# IsoPowerSupply.net
KiCad netlist of a schematic drawn in Altium Designer
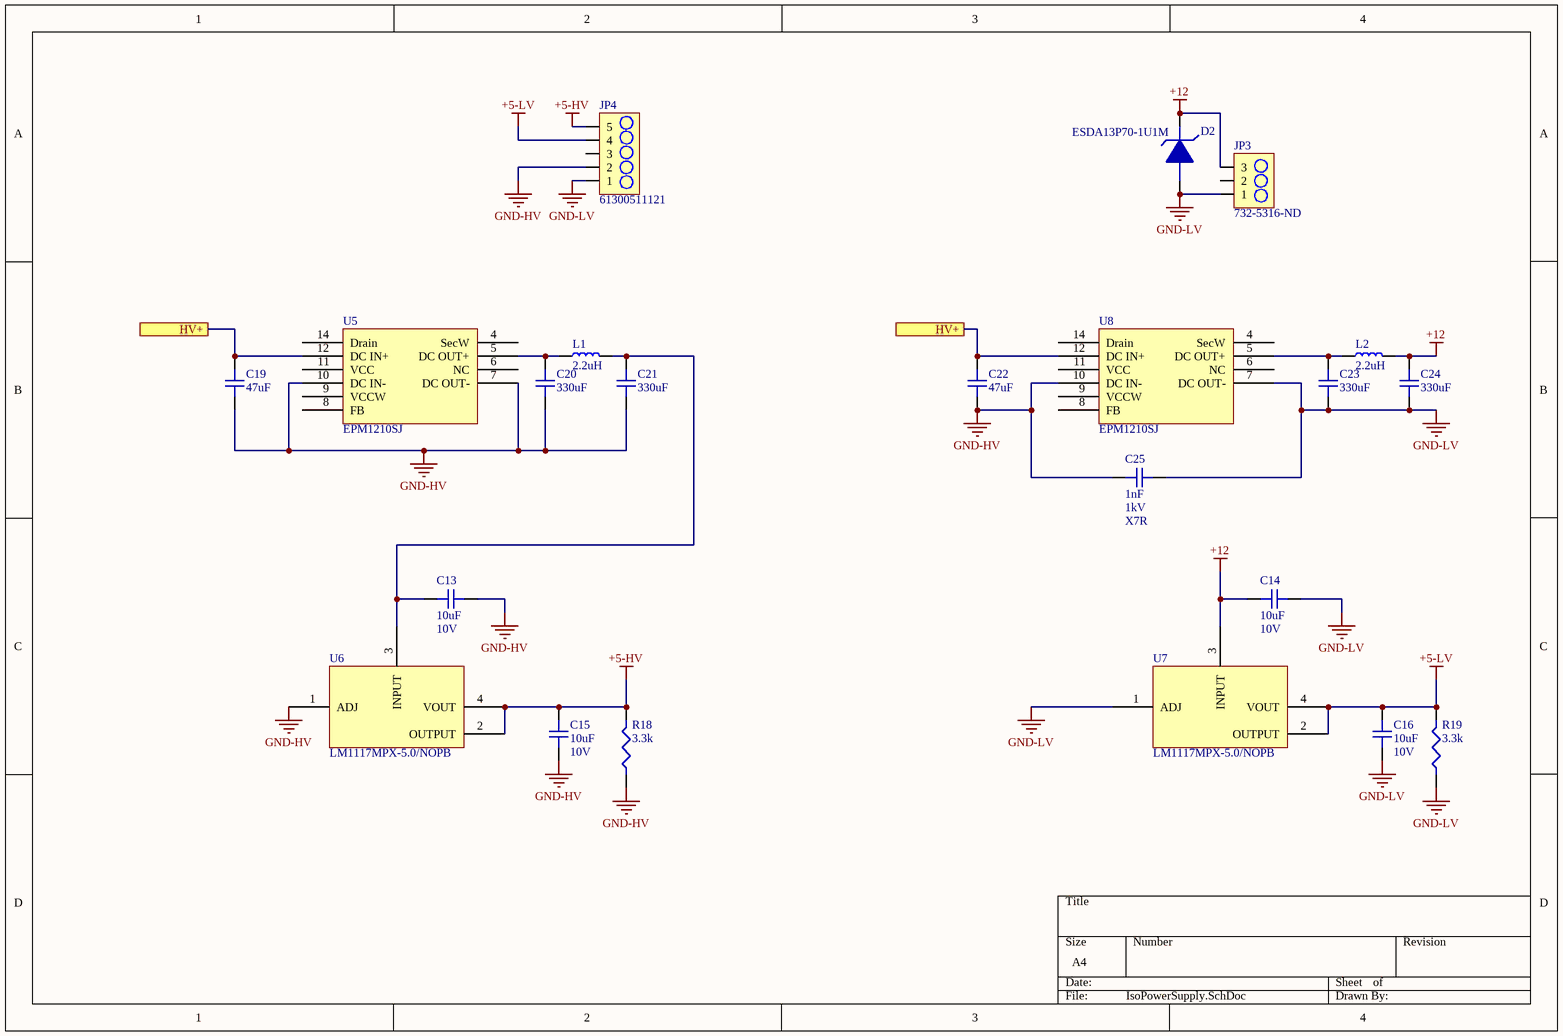
[diagram p0: IsoPowerSupply.SchDoc]

(export (version "E")
  (design (tool "Eeschema 10.0.6"))
  (components
    (comp (ref "C13")
      (value "10uF")
      (footprint "TANT_10u")
      (fields
        (field (name "MANUFACTURER") "Kyocera AVX")
        (field (name "MANUFACTURER PART NUMBER") "F381A106MMA")
        (field (name "TOLERANCE") "20%")
        (field (name "VOLTAGE RATING") "10V")
      )
      (libsource (lib "PHANTOM_LIBRARY") (part "F381A106MMA"))
    )
    (comp (ref "C14")
      (value "10uF")
      (footprint "TANT_10u")
      (fields
        (field (name "MANUFACTURER") "Kyocera AVX")
        (field (name "MANUFACTURER PART NUMBER") "F381A106MMA")
        (field (name "TOLERANCE") "20%")
        (field (name "VOLTAGE RATING") "10V")
      )
      (libsource (lib "PHANTOM_LIBRARY") (part "F381A106MMA"))
    )
    (comp (ref "C15")
      (value "10uF")
      (footprint "TANT_10u")
      (fields
        (field (name "MANUFACTURER") "Kyocera AVX")
        (field (name "MANUFACTURER PART NUMBER") "F381A106MMA")
        (field (name "TOLERANCE") "20%")
        (field (name "VOLTAGE RATING") "10V")
      )
      (libsource (lib "PHANTOM_LIBRARY") (part "F381A106MMA"))
    )
    (comp (ref "C16")
      (value "10uF")
      (footprint "TANT_10u")
      (fields
        (field (name "MANUFACTURER") "Kyocera AVX")
        (field (name "MANUFACTURER PART NUMBER") "F381A106MMA")
        (field (name "TOLERANCE") "20%")
        (field (name "VOLTAGE RATING") "10V")
      )
      (libsource (lib "PHANTOM_LIBRARY") (part "F381A106MMA"))
    )
    (comp (ref "C19")
      (value "47uF")
      (footprint "radial cap, 5mm spacing")
      (description "CAP  47µF 100V Aluminum Electrolytic Capacitors Radial, Can 2000 Hrs @ 85°C")
      (fields
        (field (name "MANUFACTURER") "Nichicon")
        (field (name "MANUFACTURER PART NUMBER") "UKL2A470KPD")
      )
      (libsource (lib "PHANTOM_LIBRARY") (part "UKL2A470KPD"))
    )
    (comp (ref "C20")
      (value "330uF")
      (footprint "radial cap, 5mm spacing")
      (description "CAP 330µF 50V Aluminum Electrolytic Capacitors Radial, Can 2000 Hrs @ 85°C")
      (fields
        (field (name "MANUFACTURER") "Nichicon")
        (field (name "MANUFACTURER PART NUMBER") "UKL1H331KHD")
      )
      (libsource (lib "PHANTOM_LIBRARY") (part "UKL1H331KHD"))
    )
    (comp (ref "C21")
      (value "330uF")
      (footprint "radial cap, 5mm spacing")
      (description "CAP 330µF 50V Aluminum Electrolytic Capacitors Radial, Can 2000 Hrs @ 85°C")
      (fields
        (field (name "MANUFACTURER") "Nichicon")
        (field (name "MANUFACTURER PART NUMBER") "UKL1H331KHD")
      )
      (libsource (lib "PHANTOM_LIBRARY") (part "UKL1H331KHD"))
    )
    (comp (ref "C22")
      (value "47uF")
      (footprint "radial cap, 5mm spacing")
      (description "CAP  47µF 100V Aluminum Electrolytic Capacitors Radial, Can 2000 Hrs @ 85°C")
      (fields
        (field (name "MANUFACTURER") "Nichicon")
        (field (name "MANUFACTURER PART NUMBER") "UKL2A470KPD")
      )
      (libsource (lib "PHANTOM_LIBRARY") (part "UKL2A470KPD"))
    )
    (comp (ref "C23")
      (value "330uF")
      (footprint "radial cap, 5mm spacing")
      (description "CAP 330µF 50V Aluminum Electrolytic Capacitors Radial, Can 2000 Hrs @ 85°C")
      (fields
        (field (name "MANUFACTURER") "Nichicon")
        (field (name "MANUFACTURER PART NUMBER") "UKL1H331KHD")
      )
      (libsource (lib "PHANTOM_LIBRARY") (part "UKL1H331KHD"))
    )
    (comp (ref "C24")
      (value "330uF")
      (footprint "radial cap, 5mm spacing")
      (description "CAP 330µF 50V Aluminum Electrolytic Capacitors Radial, Can 2000 Hrs @ 85°C")
      (fields
        (field (name "MANUFACTURER") "Nichicon")
        (field (name "MANUFACTURER PART NUMBER") "UKL1H331KHD")
      )
      (libsource (lib "PHANTOM_LIBRARY") (part "UKL1H331KHD"))
    )
    (comp (ref "C25")
      (value "1nF")
      (footprint "C1206")
      (description "CAP MLCC 1000PF 1KV X7R 1206 Series Comm. Isolation Caps")
      (fields
        (field (name "MANUFACTURER") "Yageo")
        (field (name "MANUFACTURER PART NUMBER") "CC1206KKX7RCBB102")
        (field (name "VOLTAGE RATING") "1kV")
        (field (name "DIELECTRIC") "X7R")
      )
      (libsource (lib "PHANTOM_LIBRARY") (part "CC1206KKX7RCBB102"))
    )
    (comp (ref "D2")
      (value "ESDA13P70-1U1M")
      (footprint "DIODE_TVS_0603")
      (description "TVS diode 12V, 20V Clamp 60A (8/20µs) Ipp Tvs Diode Surface Mount 1610")
      (fields (field (name "MANUFACTURER") "STMicroelectronics"))
      (libsource (lib "PHANTOM_LIBRARY") (part "ESDA13P70-1U1M"))
    )
    (comp (ref "JP3")
      (value "732-5316-ND")
      (footprint "3PIN_HEADER")
      (fields
        (field (name "MANUFACTURER") "Wurth Electronics")
        (field (name "MANUFACTURER PART NUMBER") "61300311121")
      )
      (libsource (lib "PHANTOM_LIBRARY") (part "61300311121"))
    )
    (comp (ref "JP4")
      (value "61300511121")
      (footprint "5PIN_HEADER")
      (fields (field (name "MANUFACTURER") "Wurth Electronics"))
      (libsource (lib "PHANTOM_LIBRARY") (part "61300511121"))
    )
    (comp (ref "L1")
      (value "2.2uH")
      (footprint "L0805")
      (description "IND 2.2µH Shielded Wirewound Inductor 1.2A 228mOhm Max 0805 (2012 Metric)")
      (fields
        (field (name "MANUFACTURER") "Murata")
        (field (name "MANUFACTURER PART NUMBER") "DFE201210U-2R2M=P2")
      )
      (libsource (lib "PHANTOM_LIBRARY") (part "DFE201210U-2R2M=P2"))
    )
    (comp (ref "L2")
      (value "2.2uH")
      (footprint "L0805")
      (description "IND 2.2µH Shielded Wirewound Inductor 1.2A 228mOhm Max 0805 (2012 Metric)")
      (fields
        (field (name "MANUFACTURER") "Murata")
        (field (name "MANUFACTURER PART NUMBER") "DFE201210U-2R2M=P2")
      )
      (libsource (lib "PHANTOM_LIBRARY") (part "DFE201210U-2R2M=P2"))
    )
    (comp (ref "R18")
      (value "3.3k")
      (footprint "R0805")
      (description "RES SMD 3.3k OHM 0805 3.3k Ohm 0.1% 0.125W(1/8W) ±25ppm/C Molded SMD Automotive Punched T/R")
      (fields
        (field (name "MANUFACTURER") "Panasonic ECG")
        (field (name "MANUFACTURER PART NUMBER") "ERA-6AEB102V")
      )
      (libsource (lib "PHANTOM_LIBRARY") (part "ERA-6AEB332V"))
    )
    (comp (ref "R19")
      (value "3.3k")
      (footprint "R0805")
      (description "RES SMD 3.3k OHM 0805 3.3k Ohm 0.1% 0.125W(1/8W) ±25ppm/C Molded SMD Automotive Punched T/R")
      (fields
        (field (name "MANUFACTURER") "Panasonic ECG")
        (field (name "MANUFACTURER PART NUMBER") "ERA-6AEB102V")
      )
      (libsource (lib "PHANTOM_LIBRARY") (part "ERA-6AEB332V"))
    )
    (comp (ref "U5")
      (value "EPM1210SJ")
      (footprint "14-DIP Module")
      (description "Isolated Module DC DC Converter 1 Output 12V 1A 110V - 450V Input")
      (fields (field (name "MANUFACTURER") "Tamura") (field (name "POWER") "12W"))
      (libsource (lib "PHANTOM_LIBRARY") (part "EPM1210SJ"))
    )
    (comp (ref "U6")
      (value "LM1117MPX-5.0/NOPB")
      (footprint "LM1117MPX-5.0/NOPB")
      (description "IC REG LINEAR 5V 800MA SOT223-4")
      (fields
        (field (name "MANUFACTURER") "Texas Instruments")
        (field (name "MANUFACTURER PART NUMBER") "NKE0503SC")
      )
      (libsource (lib "PHANTOM_LIBRARY") (part "LM1117MPX-5.0/NOPB"))
    )
    (comp (ref "U7")
      (value "LM1117MPX-5.0/NOPB")
      (footprint "LM1117MPX-5.0/NOPB")
      (description "IC REG LINEAR 5V 800MA SOT223-4")
      (fields
        (field (name "MANUFACTURER") "Texas Instruments")
        (field (name "MANUFACTURER PART NUMBER") "NKE0503SC")
      )
      (libsource (lib "PHANTOM_LIBRARY") (part "LM1117MPX-5.0/NOPB"))
    )
    (comp (ref "U8")
      (value "EPM1210SJ")
      (footprint "14-DIP Module")
      (description "Isolated Module DC DC Converter 1 Output 12V 1A 110V - 450V Input")
      (fields (field (name "MANUFACTURER") "Tamura") (field (name "POWER") "12W"))
      (libsource (lib "PHANTOM_LIBRARY") (part "EPM1210SJ"))
    )
  )
  (nets
    (net (code "1") (name "+5-HV") (class "Default")
      (node (ref "C15") (pin "2") (pinfunction "2_2") (pintype "passive"))
      (node (ref "JP4") (pin "5") (pinfunction "5_5") (pintype "passive"))
      (node (ref "R18") (pin "2") (pinfunction "2_2") (pintype "passive"))
      (node (ref "U6") (pin "2") (pinfunction "OUTPUT_2") (pintype "passive"))
      (node (ref "U6") (pin "4") (pinfunction "VOUT_4") (pintype "passive"))
    )
    (net (code "2") (name "+5-LV") (class "Default")
      (node (ref "C16") (pin "2") (pinfunction "2_2") (pintype "passive"))
      (node (ref "JP4") (pin "4") (pinfunction "4_4") (pintype "passive"))
      (node (ref "R19") (pin "2") (pinfunction "2_2") (pintype "passive"))
      (node (ref "U7") (pin "2") (pinfunction "OUTPUT_2") (pintype "passive"))
      (node (ref "U7") (pin "4") (pinfunction "VOUT_4") (pintype "passive"))
    )
    (net (code "3") (name "+12") (class "Default")
      (node (ref "C14") (pin "1") (pinfunction "1_1") (pintype "passive"))
      (node (ref "C24") (pin "2") (pinfunction "2_2") (pintype "passive"))
      (node (ref "D2") (pin "1") (pinfunction "2_1") (pintype "passive"))
      (node (ref "JP3") (pin "3") (pinfunction "3_3") (pintype "passive"))
      (node (ref "L2") (pin "2") (pinfunction "2_2") (pintype "passive"))
      (node (ref "U7") (pin "3") (pinfunction "INPUT_3") (pintype "passive"))
    )
    (net (code "4") (name "/HV+") (class "Default")
      (node (ref "C19") (pin "2") (pinfunction "2_2") (pintype "passive"))
      (node (ref "C22") (pin "2") (pinfunction "2_2") (pintype "passive"))
      (node (ref "U5") (pin "12") (pinfunction "DC_IN+_12") (pintype "passive"))
      (node (ref "U8") (pin "12") (pinfunction "DC_IN+_12") (pintype "passive"))
    )
    (net (code "5") (name "GND-HV") (class "Default")
      (node (ref "C13") (pin "2") (pinfunction "2_2") (pintype "passive"))
      (node (ref "C15") (pin "1") (pinfunction "1_1") (pintype "passive"))
      (node (ref "C19") (pin "1") (pinfunction "1_1") (pintype "passive"))
      (node (ref "C20") (pin "1") (pinfunction "1_1") (pintype "passive"))
      (node (ref "C21") (pin "1") (pinfunction "1_1") (pintype "passive"))
      (node (ref "C22") (pin "1") (pinfunction "1_1") (pintype "passive"))
      (node (ref "C25") (pin "1") (pinfunction "1_1") (pintype "passive"))
      (node (ref "JP4") (pin "2") (pinfunction "2_2") (pintype "passive"))
      (node (ref "R18") (pin "1") (pinfunction "1_1") (pintype "passive"))
      (node (ref "U5") (pin "10") (pinfunction "DC_IN-_10") (pintype "passive"))
      (node (ref "U5") (pin "7") (pinfunction "DC_OUT-_7") (pintype "passive"))
      (node (ref "U6") (pin "1") (pinfunction "ADJ_1") (pintype "passive"))
      (node (ref "U8") (pin "10") (pinfunction "DC_IN-_10") (pintype "passive"))
    )
    (net (code "6") (name "GND-LV") (class "Default")
      (node (ref "C14") (pin "2") (pinfunction "2_2") (pintype "passive"))
      (node (ref "C16") (pin "1") (pinfunction "1_1") (pintype "passive"))
      (node (ref "C23") (pin "1") (pinfunction "1_1") (pintype "passive"))
      (node (ref "C24") (pin "1") (pinfunction "1_1") (pintype "passive"))
      (node (ref "C25") (pin "2") (pinfunction "2_2") (pintype "passive"))
      (node (ref "D2") (pin "2") (pinfunction "1_2") (pintype "passive"))
      (node (ref "JP3") (pin "1") (pinfunction "1_1") (pintype "passive"))
      (node (ref "JP4") (pin "1") (pinfunction "1_1") (pintype "passive"))
      (node (ref "R19") (pin "1") (pinfunction "1_1") (pintype "passive"))
      (node (ref "U7") (pin "1") (pinfunction "ADJ_1") (pintype "passive"))
      (node (ref "U8") (pin "7") (pinfunction "DC_OUT-_7") (pintype "passive"))
    )
    (net (code "7") (name "Net-(U5-DC_OUT+)") (class "Default")
      (node (ref "C20") (pin "2") (pinfunction "2_2") (pintype "passive"))
      (node (ref "L1") (pin "1") (pinfunction "1_1") (pintype "passive"))
      (node (ref "U5") (pin "5") (pinfunction "DC_OUT+_5") (pintype "passive"))
    )
    (net (code "8") (name "Net-(U6-INPUT)") (class "Default")
      (node (ref "C13") (pin "1") (pinfunction "1_1") (pintype "passive"))
      (node (ref "C21") (pin "2") (pinfunction "2_2") (pintype "passive"))
      (node (ref "L1") (pin "2") (pinfunction "2_2") (pintype "passive"))
      (node (ref "U6") (pin "3") (pinfunction "INPUT_3") (pintype "passive"))
    )
    (net (code "9") (name "Net-(U8-DC_OUT+)") (class "Default")
      (node (ref "C23") (pin "2") (pinfunction "2_2") (pintype "passive"))
      (node (ref "L2") (pin "1") (pinfunction "1_1") (pintype "passive"))
      (node (ref "U8") (pin "5") (pinfunction "DC_OUT+_5") (pintype "passive"))
    )
    (net (code "10") (name "unconnected-(JP3-Pad2)") (class "Default")
      (node (ref "JP3") (pin "2") (pinfunction "2_2") (pintype "passive"))
    )
    (net (code "11") (name "unconnected-(JP4-Pad3)") (class "Default")
      (node (ref "JP4") (pin "3") (pinfunction "3_3") (pintype "passive"))
    )
    (net (code "12") (name "unconnected-(U5-Drain-Pad14)") (class "Default")
      (node (ref "U5") (pin "14") (pinfunction "Drain_14") (pintype "passive"))
    )
    (net (code "13") (name "unconnected-(U5-FB-Pad8)") (class "Default")
      (node (ref "U5") (pin "8") (pinfunction "FB_8") (pintype "passive"))
    )
    (net (code "14") (name "unconnected-(U5-NC-Pad6)") (class "Default")
      (node (ref "U5") (pin "6") (pinfunction "NC_6") (pintype "passive"))
    )
    (net (code "15") (name "unconnected-(U5-SecW-Pad4)") (class "Default")
      (node (ref "U5") (pin "4") (pinfunction "SecW_4") (pintype "passive"))
    )
    (net (code "16") (name "unconnected-(U5-VCC-Pad11)") (class "Default")
      (node (ref "U5") (pin "11") (pinfunction "VCC_11") (pintype "passive"))
    )
    (net (code "17") (name "unconnected-(U5-VCCW-Pad9)") (class "Default")
      (node (ref "U5") (pin "9") (pinfunction "VCCW_9") (pintype "passive"))
    )
    (net (code "18") (name "unconnected-(U8-Drain-Pad14)") (class "Default")
      (node (ref "U8") (pin "14") (pinfunction "Drain_14") (pintype "passive"))
    )
    (net (code "19") (name "unconnected-(U8-FB-Pad8)") (class "Default")
      (node (ref "U8") (pin "8") (pinfunction "FB_8") (pintype "passive"))
    )
    (net (code "20") (name "unconnected-(U8-NC-Pad6)") (class "Default")
      (node (ref "U8") (pin "6") (pinfunction "NC_6") (pintype "passive"))
    )
    (net (code "21") (name "unconnected-(U8-SecW-Pad4)") (class "Default")
      (node (ref "U8") (pin "4") (pinfunction "SecW_4") (pintype "passive"))
    )
    (net (code "22") (name "unconnected-(U8-VCC-Pad11)") (class "Default")
      (node (ref "U8") (pin "11") (pinfunction "VCC_11") (pintype "passive"))
    )
    (net (code "23") (name "unconnected-(U8-VCCW-Pad9)") (class "Default")
      (node (ref "U8") (pin "9") (pinfunction "VCCW_9") (pintype "passive"))
    )
  )
)
